# LCD_b.net
KiCad netlist of a schematic drawn in EAGLE
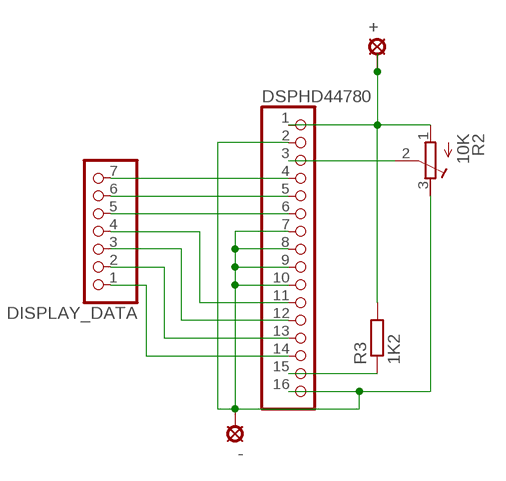
[diagram p0: schematic, sheet 1]

(export (version "E")
  (design (tool "Eeschema 10.0.6"))
  (components
    (comp (ref "+")
      (value "LSP10")
      (footprint "eagle-import:LSP10")
      (libsource (lib "eagle-import") (part "LSP10"))
    )
    (comp (ref "-")
      (value "LSP10")
      (footprint "eagle-import:LSP10")
      (libsource (lib "eagle-import") (part "LSP10"))
    )
    (comp (ref "DISPLAY_DATA")
      (value "PINHD-1X7")
      (footprint "eagle-import:1X07")
      (libsource (lib "eagle-import") (part "PINHD-1X7"))
    )
    (comp (ref "DSPHD44780")
      (value "PINHD-1X16")
      (footprint "eagle-import:1X16")
      (libsource (lib "eagle-import") (part "PINHD-1X16"))
    )
    (comp (ref "R2")
      (value "10K")
      (footprint "eagle-import:RTRIM3339P")
      (libsource (lib "eagle-import") (part "R-TRIMM3339P"))
    )
    (comp (ref "R3")
      (value "1K2")
      (footprint "eagle-import:0207_10")
      (libsource (lib "eagle-import") (part "R-EU_0207/10"))
    )
  )
  (nets
    (net (code "1") (name "Net-(DISPLAY_DATA-Pad1)") (class "Default")
      (node (ref "DISPLAY_DATA") (pin "1") (pinfunction "1_1") (pintype "passive"))
      (node (ref "DSPHD44780") (pin "14") (pinfunction "14_14") (pintype "passive"))
    )
    (net (code "2") (name "Net-(DISPLAY_DATA-Pad2)") (class "Default")
      (node (ref "DISPLAY_DATA") (pin "2") (pinfunction "2_2") (pintype "passive"))
      (node (ref "DSPHD44780") (pin "13") (pinfunction "13_13") (pintype "passive"))
    )
    (net (code "3") (name "Net-(DISPLAY_DATA-Pad3)") (class "Default")
      (node (ref "DISPLAY_DATA") (pin "3") (pinfunction "3_3") (pintype "passive"))
      (node (ref "DSPHD44780") (pin "12") (pinfunction "12_12") (pintype "passive"))
    )
    (net (code "4") (name "Net-(DISPLAY_DATA-Pad4)") (class "Default")
      (node (ref "DISPLAY_DATA") (pin "4") (pinfunction "4_4") (pintype "passive"))
      (node (ref "DSPHD44780") (pin "11") (pinfunction "11_11") (pintype "passive"))
    )
    (net (code "5") (name "Net-(DISPLAY_DATA-Pad5)") (class "Default")
      (node (ref "DISPLAY_DATA") (pin "5") (pinfunction "5_5") (pintype "passive"))
      (node (ref "DSPHD44780") (pin "6") (pinfunction "6_6") (pintype "passive"))
    )
    (net (code "6") (name "Net-(DISPLAY_DATA-Pad6)") (class "Default")
      (node (ref "DISPLAY_DATA") (pin "6") (pinfunction "6_6") (pintype "passive"))
      (node (ref "DSPHD44780") (pin "5") (pinfunction "5_5") (pintype "passive"))
    )
    (net (code "7") (name "Net-(DISPLAY_DATA-Pad7)") (class "Default")
      (node (ref "DISPLAY_DATA") (pin "7") (pinfunction "7_7") (pintype "passive"))
      (node (ref "DSPHD44780") (pin "4") (pinfunction "4_4") (pintype "passive"))
    )
    (net (code "8") (name "Net-(DSPHD44780-Pad15)") (class "Default")
      (node (ref "DSPHD44780") (pin "15") (pinfunction "15_15") (pintype "passive"))
      (node (ref "R3") (pin "1") (pinfunction "1_1") (pintype "passive"))
    )
    (net (code "9") (name "Net-(R2-A)") (class "Default")
      (node (ref "+") (pin "MP") (pinfunction "MP_MP") (pintype "passive"))
      (node (ref "DSPHD44780") (pin "1") (pinfunction "1_1") (pintype "passive"))
      (node (ref "R2") (pin "1") (pinfunction "A_1") (pintype "passive"))
      (node (ref "R3") (pin "2") (pinfunction "2_2") (pintype "passive"))
    )
    (net (code "10") (name "Net-(R2-E)") (class "Default")
      (node (ref "-") (pin "MP") (pinfunction "MP_MP") (pintype "passive"))
      (node (ref "DSPHD44780") (pin "10") (pinfunction "10_10") (pintype "passive"))
      (node (ref "DSPHD44780") (pin "16") (pinfunction "16_16") (pintype "passive"))
      (node (ref "DSPHD44780") (pin "2") (pinfunction "2_2") (pintype "passive"))
      (node (ref "DSPHD44780") (pin "7") (pinfunction "7_7") (pintype "passive"))
      (node (ref "DSPHD44780") (pin "8") (pinfunction "8_8") (pintype "passive"))
      (node (ref "DSPHD44780") (pin "9") (pinfunction "9_9") (pintype "passive"))
      (node (ref "R2") (pin "3") (pinfunction "E_3") (pintype "passive"))
    )
    (net (code "11") (name "Net-(R2-S)") (class "Default")
      (node (ref "DSPHD44780") (pin "3") (pinfunction "3_3") (pintype "passive"))
      (node (ref "R2") (pin "2") (pinfunction "S_2") (pintype "passive"))
    )
  )
)
